# pcb.net
KiCad netlist of a schematic drawn in EAGLE
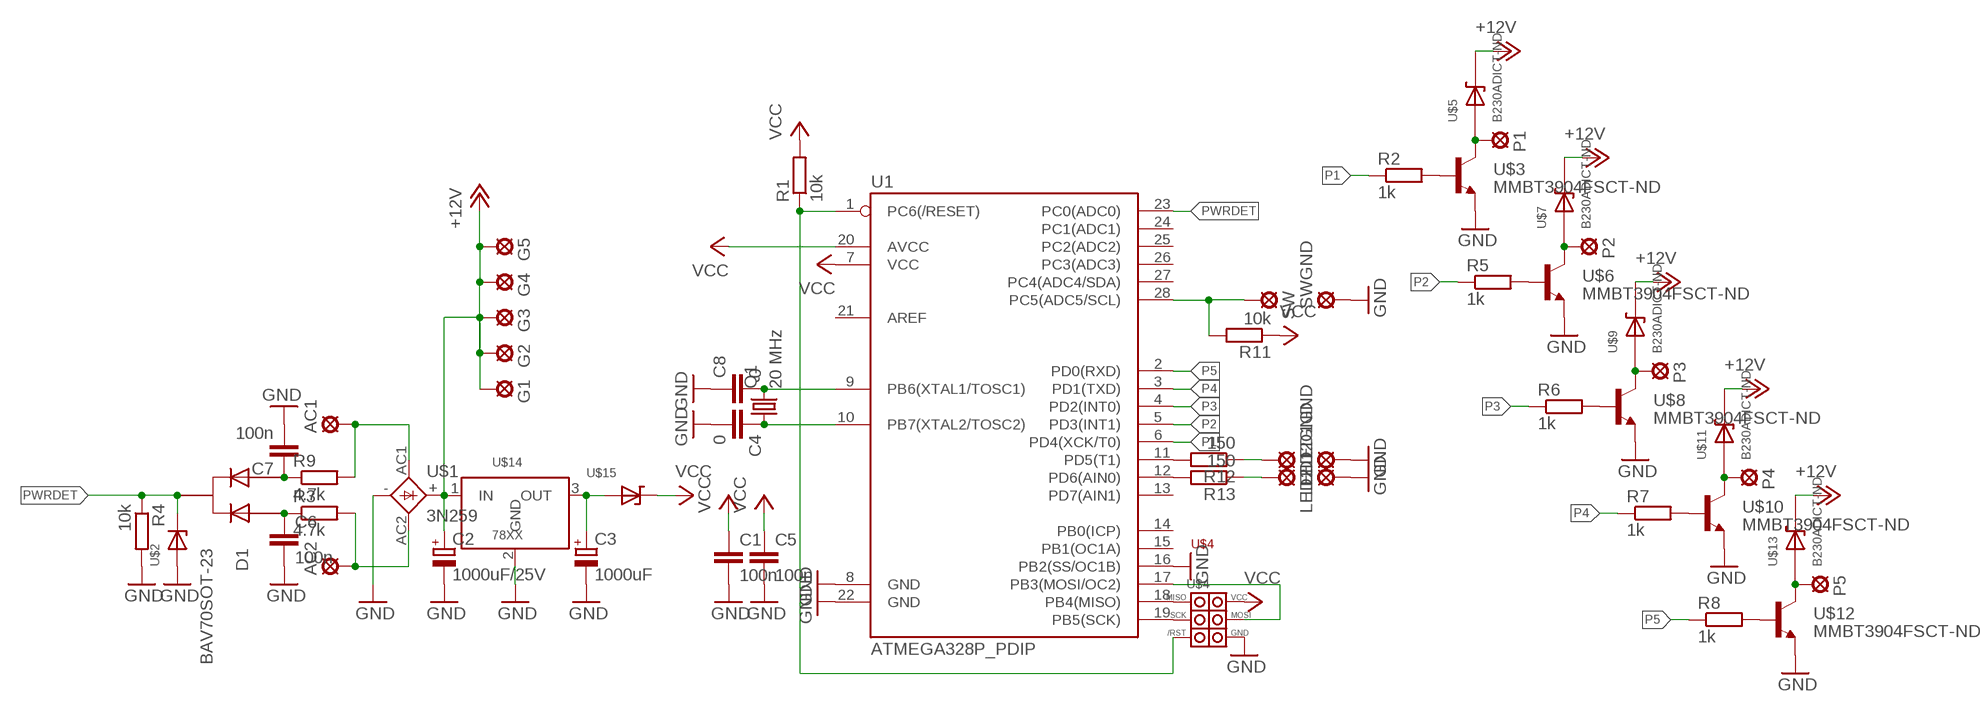
[diagram p0: schematic, sheet 1]

(export (version "E")
  (design (tool "Eeschema 10.0.6"))
  (components
    (comp (ref "AC1")
      (value "LSP10")
      (footprint "eagle-import:LSP10")
      (libsource (lib "eagle-import") (part "LSP10"))
    )
    (comp (ref "AC2")
      (value "LSP10")
      (footprint "eagle-import:LSP10")
      (libsource (lib "eagle-import") (part "LSP10"))
    )
    (comp (ref "C1")
      (value "100n")
      (footprint "eagle-import:C0603")
      (libsource (lib "eagle-import") (part "C-EUC0603"))
    )
    (comp (ref "C2")
      (value "1000uF/25V")
      (footprint "eagle-import:E5-13")
      (libsource (lib "eagle-import") (part "CPOL-EUE5-13"))
    )
    (comp (ref "C3")
      (value "1000uF")
      (footprint "eagle-import:E5-10,5")
      (libsource (lib "eagle-import") (part "CPOL-EUE5-10.5"))
    )
    (comp (ref "C4")
      (value "0")
      (footprint "eagle-import:C0603")
      (libsource (lib "eagle-import") (part "C-EUC0603"))
    )
    (comp (ref "C5")
      (value "100n")
      (footprint "eagle-import:C0603")
      (libsource (lib "eagle-import") (part "C-EUC0603"))
    )
    (comp (ref "C6")
      (value "100n")
      (footprint "eagle-import:C0603")
      (libsource (lib "eagle-import") (part "C-EUC0603"))
    )
    (comp (ref "C7")
      (value "100n")
      (footprint "eagle-import:C0603")
      (libsource (lib "eagle-import") (part "C-EUC0603"))
    )
    (comp (ref "C8")
      (value "0")
      (footprint "eagle-import:C0603")
      (libsource (lib "eagle-import") (part "C-EUC0603"))
    )
    (comp (ref "D1")
      (value "BAV70SOT-23")
      (footprint "eagle-import:SOT23")
      (libsource (lib "eagle-import") (part "BAV70SOT-23"))
    )
    (comp (ref "G1")
      (value "LSP10")
      (footprint "eagle-import:LSP10")
      (libsource (lib "eagle-import") (part "LSP10"))
    )
    (comp (ref "G2")
      (value "LSP10")
      (footprint "eagle-import:LSP10")
      (libsource (lib "eagle-import") (part "LSP10"))
    )
    (comp (ref "G3")
      (value "LSP10")
      (footprint "eagle-import:LSP10")
      (libsource (lib "eagle-import") (part "LSP10"))
    )
    (comp (ref "G4")
      (value "LSP10")
      (footprint "eagle-import:LSP10")
      (libsource (lib "eagle-import") (part "LSP10"))
    )
    (comp (ref "G5")
      (value "LSP10")
      (footprint "eagle-import:LSP10")
      (libsource (lib "eagle-import") (part "LSP10"))
    )
    (comp (ref "LED1")
      (value "LSP10")
      (footprint "eagle-import:LSP10")
      (libsource (lib "eagle-import") (part "LSP10"))
    )
    (comp (ref "LED1GND")
      (value "LSP10")
      (footprint "eagle-import:LSP10")
      (libsource (lib "eagle-import") (part "LSP10"))
    )
    (comp (ref "LED2")
      (value "LSP10")
      (footprint "eagle-import:LSP10")
      (libsource (lib "eagle-import") (part "LSP10"))
    )
    (comp (ref "LED2GND")
      (value "LSP10")
      (footprint "eagle-import:LSP10")
      (libsource (lib "eagle-import") (part "LSP10"))
    )
    (comp (ref "P1")
      (value "LSP10")
      (footprint "eagle-import:LSP10")
      (libsource (lib "eagle-import") (part "LSP10"))
    )
    (comp (ref "P2")
      (value "LSP10")
      (footprint "eagle-import:LSP10")
      (libsource (lib "eagle-import") (part "LSP10"))
    )
    (comp (ref "P3")
      (value "LSP10")
      (footprint "eagle-import:LSP10")
      (libsource (lib "eagle-import") (part "LSP10"))
    )
    (comp (ref "P4")
      (value "LSP10")
      (footprint "eagle-import:LSP10")
      (libsource (lib "eagle-import") (part "LSP10"))
    )
    (comp (ref "P5")
      (value "LSP10")
      (footprint "eagle-import:LSP10")
      (libsource (lib "eagle-import") (part "LSP10"))
    )
    (comp (ref "Q1")
      (value "20 MHz")
      (footprint "eagle-import:CTS406")
      (libsource (lib "eagle-import") (part "CRYSTALCTS406CTS406"))
    )
    (comp (ref "R1")
      (value "10k")
      (footprint "eagle-import:R0603")
      (libsource (lib "eagle-import") (part "R-EU_R0603"))
    )
    (comp (ref "R2")
      (value "1k")
      (footprint "eagle-import:R0603")
      (libsource (lib "eagle-import") (part "R-EU_R0603"))
    )
    (comp (ref "R3")
      (value "4.7k")
      (footprint "eagle-import:R0603")
      (libsource (lib "eagle-import") (part "R-EU_R0603"))
    )
    (comp (ref "R4")
      (value "10k")
      (footprint "eagle-import:R0603")
      (libsource (lib "eagle-import") (part "R-EU_R0603"))
    )
    (comp (ref "R5")
      (value "1k")
      (footprint "eagle-import:R0603")
      (libsource (lib "eagle-import") (part "R-EU_R0603"))
    )
    (comp (ref "R6")
      (value "1k")
      (footprint "eagle-import:R0603")
      (libsource (lib "eagle-import") (part "R-EU_R0603"))
    )
    (comp (ref "R7")
      (value "1k")
      (footprint "eagle-import:R0603")
      (libsource (lib "eagle-import") (part "R-EU_R0603"))
    )
    (comp (ref "R8")
      (value "1k")
      (footprint "eagle-import:R0603")
      (libsource (lib "eagle-import") (part "R-EU_R0603"))
    )
    (comp (ref "R9")
      (value "4.7k")
      (footprint "eagle-import:R0603")
      (libsource (lib "eagle-import") (part "R-EU_R0603"))
    )
    (comp (ref "R11")
      (value "10k")
      (footprint "eagle-import:R0603")
      (libsource (lib "eagle-import") (part "R-EU_R0603"))
    )
    (comp (ref "R12")
      (value "150")
      (footprint "eagle-import:R0603")
      (libsource (lib "eagle-import") (part "R-EU_R0603"))
    )
    (comp (ref "R13")
      (value "150")
      (footprint "eagle-import:R0603")
      (libsource (lib "eagle-import") (part "R-EU_R0603"))
    )
    (comp (ref "SW")
      (value "LSP10")
      (footprint "eagle-import:LSP10")
      (libsource (lib "eagle-import") (part "LSP10"))
    )
    (comp (ref "SWGND")
      (value "LSP10")
      (footprint "eagle-import:LSP10")
      (libsource (lib "eagle-import") (part "LSP10"))
    )
    (comp (ref "U$1")
      (value "3N259")
      (footprint "eagle-import:KBPM")
      (libsource (lib "eagle-import") (part "3N259"))
    )
    (comp (ref "U$2")
      (value "MA8051CT")
      (footprint "eagle-import:SOD323-W")
      (libsource (lib "eagle-import") (part "MA8051CT"))
    )
    (comp (ref "U$3")
      (value "MMBT3904FSCT-ND")
      (footprint "eagle-import:SOT-23")
      (libsource (lib "eagle-import") (part "MMBT3904FSCT-ND"))
    )
    (comp (ref "U$4")
      (value "ISP-HEADER-6")
      (footprint "eagle-import:ISPHEADER-6")
      (libsource (lib "eagle-import") (part "ISP-HEADER-6"))
    )
    (comp (ref "U$5")
      (value "B230ADICT-ND")
      (footprint "eagle-import:SMA_SMB")
      (libsource (lib "eagle-import") (part "B230ADICT-ND"))
    )
    (comp (ref "U$6")
      (value "MMBT3904FSCT-ND")
      (footprint "eagle-import:SOT-23")
      (libsource (lib "eagle-import") (part "MMBT3904FSCT-ND"))
    )
    (comp (ref "U$7")
      (value "B230ADICT-ND")
      (footprint "eagle-import:SMA_SMB")
      (libsource (lib "eagle-import") (part "B230ADICT-ND"))
    )
    (comp (ref "U$8")
      (value "MMBT3904FSCT-ND")
      (footprint "eagle-import:SOT-23")
      (libsource (lib "eagle-import") (part "MMBT3904FSCT-ND"))
    )
    (comp (ref "U$9")
      (value "B230ADICT-ND")
      (footprint "eagle-import:SMA_SMB")
      (libsource (lib "eagle-import") (part "B230ADICT-ND"))
    )
    (comp (ref "U$10")
      (value "MMBT3904FSCT-ND")
      (footprint "eagle-import:SOT-23")
      (libsource (lib "eagle-import") (part "MMBT3904FSCT-ND"))
    )
    (comp (ref "U$11")
      (value "B230ADICT-ND")
      (footprint "eagle-import:SMA_SMB")
      (libsource (lib "eagle-import") (part "B230ADICT-ND"))
    )
    (comp (ref "U$12")
      (value "MMBT3904FSCT-ND")
      (footprint "eagle-import:SOT-23")
      (libsource (lib "eagle-import") (part "MMBT3904FSCT-ND"))
    )
    (comp (ref "U$13")
      (value "B230ADICT-ND")
      (footprint "eagle-import:SMA_SMB")
      (libsource (lib "eagle-import") (part "B230ADICT-ND"))
    )
    (comp (ref "U$14")
      (value "78XX")
      (footprint "eagle-import:DPAK")
      (libsource (lib "eagle-import") (part "78XX"))
    )
    (comp (ref "U$15")
      (value "MBRM140T1")
      (footprint "eagle-import:CASE457")
      (libsource (lib "eagle-import") (part "MBRM140T1"))
    )
    (comp (ref "U1")
      (value "ATMEGA328P_PDIP")
      (footprint "eagle-import:DIL28-3")
      (libsource (lib "eagle-import") (part "ATMEGA328P_PDIP"))
    )
  )
  (nets
    (net (code "1") (name "+12V") (class "Default")
      (node (ref "C2") (pin "+") (pinfunction "+_+") (pintype "passive"))
      (node (ref "G1") (pin "MP") (pinfunction "MP_MP") (pintype "passive"))
      (node (ref "G2") (pin "MP") (pinfunction "MP_MP") (pintype "passive"))
      (node (ref "G3") (pin "MP") (pinfunction "MP_MP") (pintype "passive"))
      (node (ref "G4") (pin "MP") (pinfunction "MP_MP") (pintype "passive"))
      (node (ref "G5") (pin "MP") (pinfunction "MP_MP") (pintype "passive"))
      (node (ref "U$1") (pin "+") (pinfunction "+_+") (pintype "passive"))
      (node (ref "U$11") (pin "1") (pinfunction "CAT_1") (pintype "bidirectional"))
      (node (ref "U$13") (pin "1") (pinfunction "CAT_1") (pintype "bidirectional"))
      (node (ref "U$14") (pin "1") (pinfunction "IN_1") (pintype "bidirectional"))
      (node (ref "U$5") (pin "1") (pinfunction "CAT_1") (pintype "bidirectional"))
      (node (ref "U$7") (pin "1") (pinfunction "CAT_1") (pintype "bidirectional"))
      (node (ref "U$9") (pin "1") (pinfunction "CAT_1") (pintype "bidirectional"))
    )
    (net (code "2") (name "GND") (class "Default")
      (node (ref "C1") (pin "2") (pinfunction "2_2") (pintype "passive"))
      (node (ref "C2") (pin "-") (pinfunction "-_-") (pintype "passive"))
      (node (ref "C3") (pin "-") (pinfunction "-_-") (pintype "passive"))
      (node (ref "C4") (pin "2") (pinfunction "2_2") (pintype "passive"))
      (node (ref "C5") (pin "2") (pinfunction "2_2") (pintype "passive"))
      (node (ref "C6") (pin "2") (pinfunction "2_2") (pintype "passive"))
      (node (ref "C7") (pin "2") (pinfunction "2_2") (pintype "passive"))
      (node (ref "C8") (pin "1") (pinfunction "1_1") (pintype "passive"))
      (node (ref "LED1GND") (pin "MP") (pinfunction "MP_MP") (pintype "passive"))
      (node (ref "LED2GND") (pin "MP") (pinfunction "MP_MP") (pintype "passive"))
      (node (ref "R4") (pin "2") (pinfunction "2_2") (pintype "passive"))
      (node (ref "SWGND") (pin "MP") (pinfunction "MP_MP") (pintype "passive"))
      (node (ref "U$1") (pin "-") (pinfunction "-_-") (pintype "passive"))
      (node (ref "U$10") (pin "2") (pinfunction "E_2") (pintype "passive"))
      (node (ref "U$12") (pin "2") (pinfunction "E_2") (pintype "passive"))
      (node (ref "U$14") (pin "2") (pinfunction "GND_2") (pintype "bidirectional"))
      (node (ref "U$2") (pin "A") (pinfunction "AN_A") (pintype "bidirectional"))
      (node (ref "U$3") (pin "2") (pinfunction "E_2") (pintype "passive"))
      (node (ref "U$4") (pin "GND") (pinfunction "GND_GND") (pintype "bidirectional"))
      (node (ref "U$6") (pin "2") (pinfunction "E_2") (pintype "passive"))
      (node (ref "U$8") (pin "2") (pinfunction "E_2") (pintype "passive"))
      (node (ref "U1") (pin "16") (pinfunction "PB2(SS/OC1B)_16") (pintype "bidirectional"))
      (node (ref "U1") (pin "22") (pinfunction "GND_22") (pintype "bidirectional"))
      (node (ref "U1") (pin "8") (pinfunction "GND_8") (pintype "bidirectional"))
    )
    (net (code "3") (name "Net-(AC1-PadMP)") (class "Default")
      (node (ref "AC1") (pin "MP") (pinfunction "MP_MP") (pintype "passive"))
      (node (ref "R9") (pin "2") (pinfunction "2_2") (pintype "passive"))
      (node (ref "U$1") (pin "AC1") (pinfunction "AC1_AC1") (pintype "passive"))
    )
    (net (code "4") (name "Net-(AC2-PadMP)") (class "Default")
      (node (ref "AC2") (pin "MP") (pinfunction "MP_MP") (pintype "passive"))
      (node (ref "R3") (pin "2") (pinfunction "2_2") (pintype "passive"))
      (node (ref "U$1") (pin "AC2") (pinfunction "AC2_AC2") (pintype "passive"))
    )
    (net (code "5") (name "Net-(D1-ANODE1)") (class "Default")
      (node (ref "C6") (pin "1") (pinfunction "1_1") (pintype "passive"))
      (node (ref "D1") (pin "1ANODE") (pinfunction "ANODE1_1ANODE") (pintype "input"))
      (node (ref "R3") (pin "1") (pinfunction "1_1") (pintype "passive"))
    )
    (net (code "6") (name "Net-(D1-ANODE2)") (class "Default")
      (node (ref "C7") (pin "1") (pinfunction "1_1") (pintype "passive"))
      (node (ref "D1") (pin "2ANODE") (pinfunction "ANODE2_2ANODE") (pintype "input"))
      (node (ref "R9") (pin "1") (pinfunction "1_1") (pintype "passive"))
    )
    (net (code "7") (name "Net-(LED1-PadMP)") (class "Default")
      (node (ref "LED1") (pin "MP") (pinfunction "MP_MP") (pintype "passive"))
      (node (ref "R12") (pin "1") (pinfunction "1_1") (pintype "passive"))
    )
    (net (code "8") (name "Net-(LED2-PadMP)") (class "Default")
      (node (ref "LED2") (pin "MP") (pinfunction "MP_MP") (pintype "passive"))
      (node (ref "R13") (pin "1") (pinfunction "1_1") (pintype "passive"))
    )
    (net (code "9") (name "Net-(Q1-2)") (class "Default")
      (node (ref "C8") (pin "2") (pinfunction "2_2") (pintype "passive"))
      (node (ref "Q1") (pin "3") (pinfunction "2_3") (pintype "passive"))
      (node (ref "U1") (pin "9") (pinfunction "PB6(XTAL1/TOSC1)_9") (pintype "bidirectional"))
    )
    (net (code "10") (name "Net-(U$3-B)") (class "Default")
      (node (ref "R2") (pin "2") (pinfunction "2_2") (pintype "passive"))
      (node (ref "U$3") (pin "1") (pinfunction "B_1") (pintype "passive"))
    )
    (net (code "11") (name "Net-(U$3-C)") (class "Default")
      (node (ref "P1") (pin "MP") (pinfunction "MP_MP") (pintype "passive"))
      (node (ref "U$3") (pin "3") (pinfunction "C_3") (pintype "passive"))
      (node (ref "U$5") (pin "2") (pinfunction "AN_2") (pintype "bidirectional"))
    )
    (net (code "12") (name "Net-(U$6-B)") (class "Default")
      (node (ref "R5") (pin "2") (pinfunction "2_2") (pintype "passive"))
      (node (ref "U$6") (pin "1") (pinfunction "B_1") (pintype "passive"))
    )
    (net (code "13") (name "Net-(U$6-C)") (class "Default")
      (node (ref "P2") (pin "MP") (pinfunction "MP_MP") (pintype "passive"))
      (node (ref "U$6") (pin "3") (pinfunction "C_3") (pintype "passive"))
      (node (ref "U$7") (pin "2") (pinfunction "AN_2") (pintype "bidirectional"))
    )
    (net (code "14") (name "Net-(U$8-B)") (class "Default")
      (node (ref "R6") (pin "2") (pinfunction "2_2") (pintype "passive"))
      (node (ref "U$8") (pin "1") (pinfunction "B_1") (pintype "passive"))
    )
    (net (code "15") (name "Net-(U$8-C)") (class "Default")
      (node (ref "P3") (pin "MP") (pinfunction "MP_MP") (pintype "passive"))
      (node (ref "U$8") (pin "3") (pinfunction "C_3") (pintype "passive"))
      (node (ref "U$9") (pin "2") (pinfunction "AN_2") (pintype "bidirectional"))
    )
    (net (code "16") (name "Net-(U$10-B)") (class "Default")
      (node (ref "R7") (pin "2") (pinfunction "2_2") (pintype "passive"))
      (node (ref "U$10") (pin "1") (pinfunction "B_1") (pintype "passive"))
    )
    (net (code "17") (name "Net-(U$10-C)") (class "Default")
      (node (ref "P4") (pin "MP") (pinfunction "MP_MP") (pintype "passive"))
      (node (ref "U$10") (pin "3") (pinfunction "C_3") (pintype "passive"))
      (node (ref "U$11") (pin "2") (pinfunction "AN_2") (pintype "bidirectional"))
    )
    (net (code "18") (name "Net-(U$12-B)") (class "Default")
      (node (ref "R8") (pin "2") (pinfunction "2_2") (pintype "passive"))
      (node (ref "U$12") (pin "1") (pinfunction "B_1") (pintype "passive"))
    )
    (net (code "19") (name "Net-(U$12-C)") (class "Default")
      (node (ref "P5") (pin "MP") (pinfunction "MP_MP") (pintype "passive"))
      (node (ref "U$12") (pin "3") (pinfunction "C_3") (pintype "passive"))
      (node (ref "U$13") (pin "2") (pinfunction "AN_2") (pintype "bidirectional"))
    )
    (net (code "20") (name "Net-(U$14-OUT)") (class "Default")
      (node (ref "C3") (pin "+") (pinfunction "+_+") (pintype "passive"))
      (node (ref "U$14") (pin "3") (pinfunction "OUT_3") (pintype "bidirectional"))
      (node (ref "U$15") (pin "2") (pinfunction "AN_2") (pintype "bidirectional"))
    )
    (net (code "21") (name "Net-(U1-PB3(MOSI{slash}OC2))") (class "Default")
      (node (ref "U$4") (pin "MOSI") (pinfunction "MOSI_MOSI") (pintype "bidirectional"))
      (node (ref "U1") (pin "17") (pinfunction "PB3(MOSI/OC2)_17") (pintype "bidirectional"))
    )
    (net (code "22") (name "Net-(U1-PB4(MISO))") (class "Default")
      (node (ref "U$4") (pin "MISO") (pinfunction "MISO_MISO") (pintype "bidirectional"))
      (node (ref "U1") (pin "18") (pinfunction "PB4(MISO)_18") (pintype "bidirectional"))
    )
    (net (code "23") (name "Net-(U1-PB5(SCK))") (class "Default")
      (node (ref "U$4") (pin "SCK") (pinfunction "SCK_SCK") (pintype "bidirectional"))
      (node (ref "U1") (pin "19") (pinfunction "PB5(SCK)_19") (pintype "bidirectional"))
    )
    (net (code "24") (name "Net-(U1-PB7(XTAL2{slash}TOSC2))") (class "Default")
      (node (ref "C4") (pin "1") (pinfunction "1_1") (pintype "passive"))
      (node (ref "Q1") (pin "1") (pinfunction "1_1") (pintype "passive"))
      (node (ref "U1") (pin "10") (pinfunction "PB7(XTAL2/TOSC2)_10") (pintype "bidirectional"))
    )
    (net (code "25") (name "Net-(U1-PC5(ADC5{slash}SCL))") (class "Default")
      (node (ref "R11") (pin "2") (pinfunction "2_2") (pintype "passive"))
      (node (ref "SW") (pin "MP") (pinfunction "MP_MP") (pintype "passive"))
      (node (ref "U1") (pin "28") (pinfunction "PC5(ADC5/SCL)_28") (pintype "bidirectional"))
    )
    (net (code "26") (name "Net-(U1-PC6({slash}RESET))") (class "Default")
      (node (ref "R1") (pin "1") (pinfunction "1_1") (pintype "passive"))
      (node (ref "U$4") (pin "/RST") (pinfunction "/RST_/RST") (pintype "bidirectional"))
      (node (ref "U1") (pin "1") (pinfunction "PC6(/RESET)_1") (pintype "bidirectional"))
    )
    (net (code "27") (name "Net-(U1-PD5(T1))") (class "Default")
      (node (ref "R12") (pin "2") (pinfunction "2_2") (pintype "passive"))
      (node (ref "U1") (pin "11") (pinfunction "PD5(T1)_11") (pintype "bidirectional"))
    )
    (net (code "28") (name "Net-(U1-PD6(AIN0))") (class "Default")
      (node (ref "R13") (pin "2") (pinfunction "2_2") (pintype "passive"))
      (node (ref "U1") (pin "12") (pinfunction "PD6(AIN0)_12") (pintype "bidirectional"))
    )
    (net (code "29") (name "P1") (class "Default")
      (node (ref "R2") (pin "1") (pinfunction "1_1") (pintype "passive"))
      (node (ref "U1") (pin "6") (pinfunction "PD4(XCK/T0)_6") (pintype "bidirectional"))
    )
    (net (code "30") (name "P2") (class "Default")
      (node (ref "R5") (pin "1") (pinfunction "1_1") (pintype "passive"))
      (node (ref "U1") (pin "5") (pinfunction "PD3(INT1)_5") (pintype "bidirectional"))
    )
    (net (code "31") (name "P3") (class "Default")
      (node (ref "R6") (pin "1") (pinfunction "1_1") (pintype "passive"))
      (node (ref "U1") (pin "4") (pinfunction "PD2(INT0)_4") (pintype "bidirectional"))
    )
    (net (code "32") (name "P4") (class "Default")
      (node (ref "R7") (pin "1") (pinfunction "1_1") (pintype "passive"))
      (node (ref "U1") (pin "3") (pinfunction "PD1(TXD)_3") (pintype "bidirectional"))
    )
    (net (code "33") (name "P5") (class "Default")
      (node (ref "R8") (pin "1") (pinfunction "1_1") (pintype "passive"))
      (node (ref "U1") (pin "2") (pinfunction "PD0(RXD)_2") (pintype "bidirectional"))
    )
    (net (code "34") (name "PWRDET") (class "Default")
      (node (ref "D1") (pin "3CATODE") (pinfunction "CATODE_3CATODE") (pintype "output"))
      (node (ref "R4") (pin "1") (pinfunction "1_1") (pintype "passive"))
      (node (ref "U$2") (pin "C") (pinfunction "CAT_C") (pintype "bidirectional"))
      (node (ref "U1") (pin "23") (pinfunction "PC0(ADC0)_23") (pintype "bidirectional"))
    )
    (net (code "35") (name "VCC") (class "Default")
      (node (ref "C1") (pin "1") (pinfunction "1_1") (pintype "passive"))
      (node (ref "C5") (pin "1") (pinfunction "1_1") (pintype "passive"))
      (node (ref "R1") (pin "2") (pinfunction "2_2") (pintype "passive"))
      (node (ref "R11") (pin "1") (pinfunction "1_1") (pintype "passive"))
      (node (ref "U$15") (pin "1") (pinfunction "CAT_1") (pintype "bidirectional"))
      (node (ref "U$4") (pin "VCC") (pinfunction "VCC_VCC") (pintype "bidirectional"))
      (node (ref "U1") (pin "20") (pinfunction "AVCC_20") (pintype "bidirectional"))
      (node (ref "U1") (pin "7") (pinfunction "VCC_7") (pintype "bidirectional"))
    )
    (net (code "36") (name "unconnected-(U1-AREF-Pad21)") (class "Default")
      (node (ref "U1") (pin "21") (pinfunction "AREF_21") (pintype "bidirectional"))
    )
    (net (code "37") (name "unconnected-(U1-PB0(ICP)-Pad14)") (class "Default")
      (node (ref "U1") (pin "14") (pinfunction "PB0(ICP)_14") (pintype "bidirectional"))
    )
    (net (code "38") (name "unconnected-(U1-PB1(OC1A)-Pad15)") (class "Default")
      (node (ref "U1") (pin "15") (pinfunction "PB1(OC1A)_15") (pintype "bidirectional"))
    )
    (net (code "39") (name "unconnected-(U1-PC1(ADC1)-Pad24)") (class "Default")
      (node (ref "U1") (pin "24") (pinfunction "PC1(ADC1)_24") (pintype "bidirectional"))
    )
    (net (code "40") (name "unconnected-(U1-PC2(ADC2)-Pad25)") (class "Default")
      (node (ref "U1") (pin "25") (pinfunction "PC2(ADC2)_25") (pintype "bidirectional"))
    )
    (net (code "41") (name "unconnected-(U1-PC3(ADC3)-Pad26)") (class "Default")
      (node (ref "U1") (pin "26") (pinfunction "PC3(ADC3)_26") (pintype "bidirectional"))
    )
    (net (code "42") (name "unconnected-(U1-PC4(ADC4{slash}SDA)-Pad27)") (class "Default")
      (node (ref "U1") (pin "27") (pinfunction "PC4(ADC4/SDA)_27") (pintype "bidirectional"))
    )
    (net (code "43") (name "unconnected-(U1-PD7(AIN1)-Pad13)") (class "Default")
      (node (ref "U1") (pin "13") (pinfunction "PD7(AIN1)_13") (pintype "bidirectional"))
    )
  )
)
